# Gerador_de_Sinais.net
KiCad netlist of a schematic drawn in EAGLE
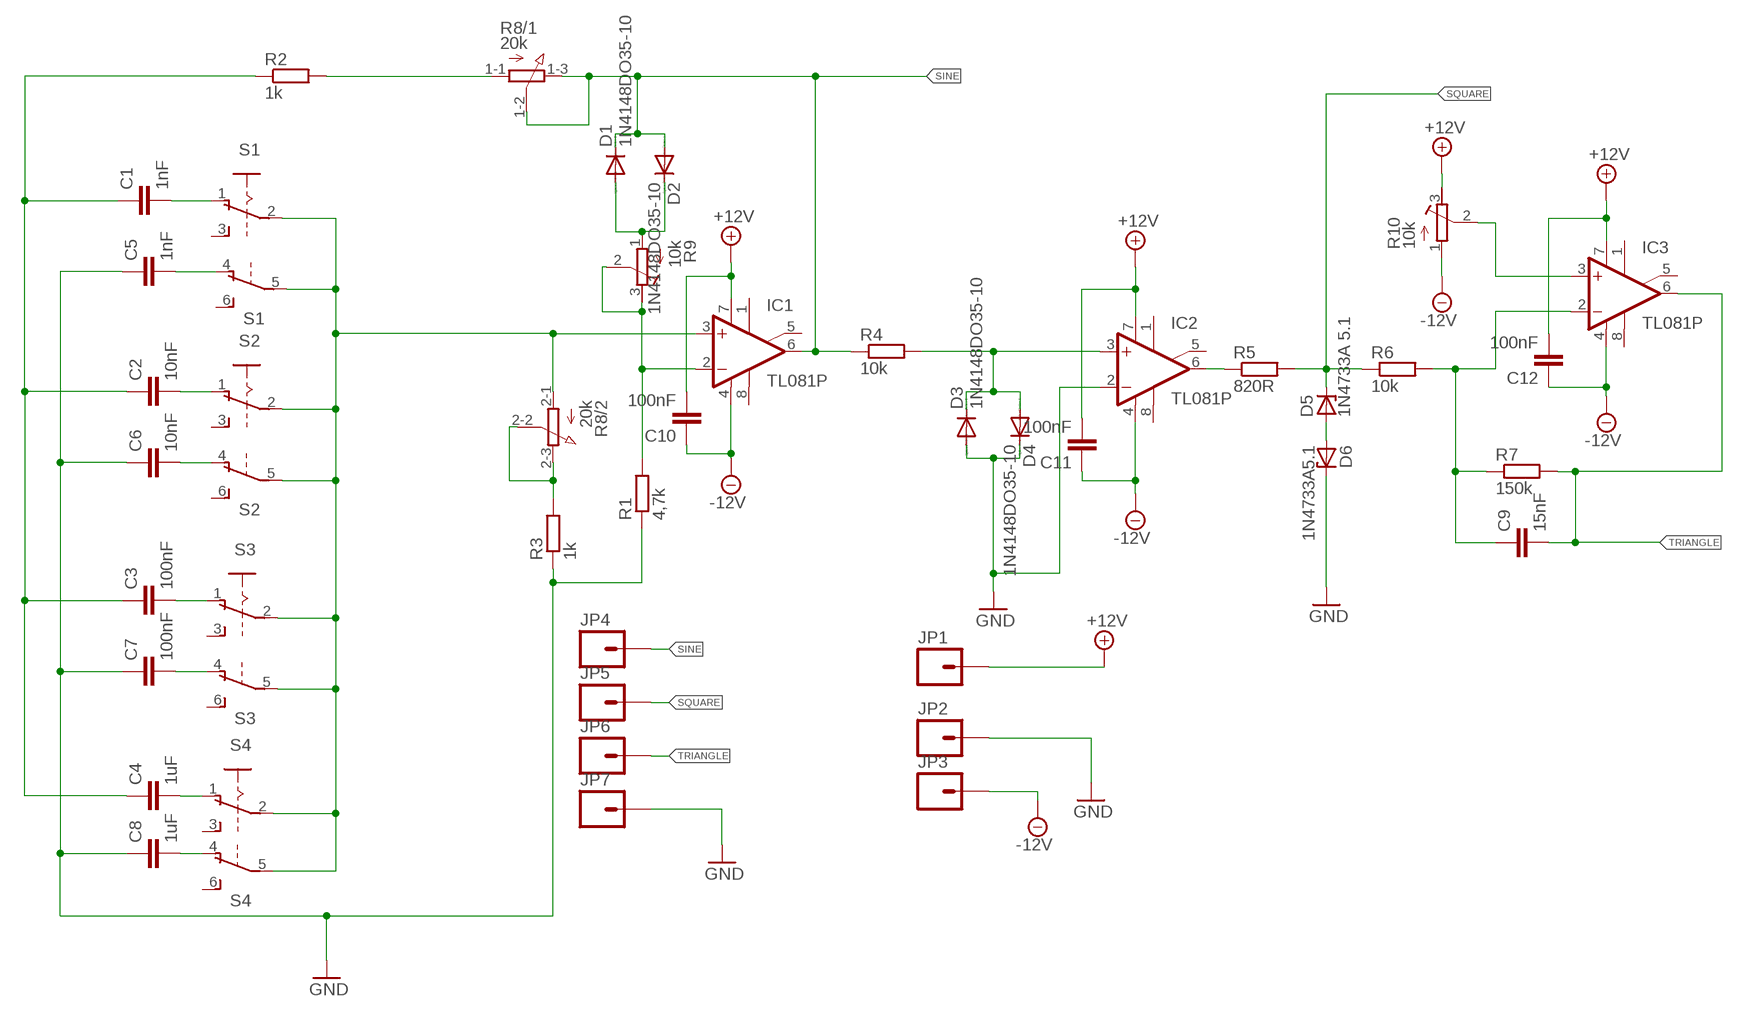
[diagram p0: schematic, sheet 1]

(export (version "E")
  (design (tool "Eeschema 10.0.6"))
  (components
    (comp (ref "C1")
      (value "1nF")
      (footprint "eagle-import:C050-050X075")
      (libsource (lib "eagle-import") (part "C-EU050-050X075"))
    )
    (comp (ref "C2")
      (value "10nF")
      (footprint "eagle-import:C050-050X075")
      (libsource (lib "eagle-import") (part "C-EU050-050X075"))
    )
    (comp (ref "C3")
      (value "100nF")
      (footprint "eagle-import:C050-050X075")
      (libsource (lib "eagle-import") (part "C-EU050-050X075"))
    )
    (comp (ref "C4")
      (value "1uF")
      (footprint "eagle-import:C050-050X075")
      (libsource (lib "eagle-import") (part "C-EU050-050X075"))
    )
    (comp (ref "C5")
      (value "1nF")
      (footprint "eagle-import:C050-050X075")
      (libsource (lib "eagle-import") (part "C-EU050-050X075"))
    )
    (comp (ref "C6")
      (value "10nF")
      (footprint "eagle-import:C050-050X075")
      (libsource (lib "eagle-import") (part "C-EU050-050X075"))
    )
    (comp (ref "C7")
      (value "100nF")
      (footprint "eagle-import:C050-050X075")
      (libsource (lib "eagle-import") (part "C-EU050-050X075"))
    )
    (comp (ref "C8")
      (value "1uF")
      (footprint "eagle-import:C050-050X075")
      (libsource (lib "eagle-import") (part "C-EU050-050X075"))
    )
    (comp (ref "C9")
      (value "15nF")
      (footprint "eagle-import:C050-050X075")
      (libsource (lib "eagle-import") (part "C-EU050-050X075"))
    )
    (comp (ref "C10")
      (value "100nF")
      (footprint "eagle-import:C050-050X075")
      (libsource (lib "eagle-import") (part "C-EU050-050X075"))
    )
    (comp (ref "C11")
      (value "100nF")
      (footprint "eagle-import:C050-050X075")
      (libsource (lib "eagle-import") (part "C-EU050-050X075"))
    )
    (comp (ref "C12")
      (value "100nF")
      (footprint "eagle-import:C050-050X075")
      (libsource (lib "eagle-import") (part "C-EU050-050X075"))
    )
    (comp (ref "D1")
      (value "1N4148DO35-10")
      (footprint "eagle-import:DO35-10")
      (libsource (lib "eagle-import") (part "1N4148DO35-10"))
    )
    (comp (ref "D2")
      (value "1N4148DO35-10")
      (footprint "eagle-import:DO35-10")
      (libsource (lib "eagle-import") (part "1N4148DO35-10"))
    )
    (comp (ref "D3")
      (value "1N4148DO35-10")
      (footprint "eagle-import:DO35-10")
      (libsource (lib "eagle-import") (part "1N4148DO35-10"))
    )
    (comp (ref "D4")
      (value "1N4148DO35-10")
      (footprint "eagle-import:DO35-10")
      (libsource (lib "eagle-import") (part "1N4148DO35-10"))
    )
    (comp (ref "D5")
      (value "1N4733A 5.1")
      (footprint "eagle-import:ZDIO-10")
      (libsource (lib "eagle-import") (part "ZENER-DIODEZD-10"))
    )
    (comp (ref "D6")
      (value "1N4733A5.1")
      (footprint "eagle-import:ZDIO-10")
      (libsource (lib "eagle-import") (part "ZENER-DIODEZD-10"))
    )
    (comp (ref "IC1")
      (value "TL081P")
      (footprint "eagle-import:DIL08")
      (libsource (lib "eagle-import") (part "TL081P"))
    )
    (comp (ref "IC2")
      (value "TL081P")
      (footprint "eagle-import:DIL08")
      (libsource (lib "eagle-import") (part "TL081P"))
    )
    (comp (ref "IC3")
      (value "TL081P")
      (footprint "eagle-import:DIL08")
      (libsource (lib "eagle-import") (part "TL081P"))
    )
    (comp (ref "JP1")
      (value "M01OFFSET")
      (footprint "eagle-import:1X01_OFFSET")
      (libsource (lib "eagle-import") (part "M01OFFSET"))
    )
    (comp (ref "JP2")
      (value "M01OFFSET")
      (footprint "eagle-import:1X01_OFFSET")
      (libsource (lib "eagle-import") (part "M01OFFSET"))
    )
    (comp (ref "JP3")
      (value "M01OFFSET")
      (footprint "eagle-import:1X01_OFFSET")
      (libsource (lib "eagle-import") (part "M01OFFSET"))
    )
    (comp (ref "JP4")
      (value "M01OFFSET")
      (footprint "eagle-import:1X01_OFFSET")
      (libsource (lib "eagle-import") (part "M01OFFSET"))
    )
    (comp (ref "JP5")
      (value "M01OFFSET")
      (footprint "eagle-import:1X01_OFFSET")
      (libsource (lib "eagle-import") (part "M01OFFSET"))
    )
    (comp (ref "JP6")
      (value "M01OFFSET")
      (footprint "eagle-import:1X01_OFFSET")
      (libsource (lib "eagle-import") (part "M01OFFSET"))
    )
    (comp (ref "JP7")
      (value "M01OFFSET")
      (footprint "eagle-import:1X01_OFFSET")
      (libsource (lib "eagle-import") (part "M01OFFSET"))
    )
    (comp (ref "R1")
      (value "4,7k")
      (footprint "eagle-import:0207_10")
      (libsource (lib "eagle-import") (part "R-EU_0207/10"))
    )
    (comp (ref "R2")
      (value "1k")
      (footprint "eagle-import:0207_10")
      (libsource (lib "eagle-import") (part "R-EU_0207/10"))
    )
    (comp (ref "R3")
      (value "1k")
      (footprint "eagle-import:0207_10")
      (libsource (lib "eagle-import") (part "R-EU_0207/10"))
    )
    (comp (ref "R4")
      (value "10k")
      (footprint "eagle-import:0207_10")
      (libsource (lib "eagle-import") (part "R-EU_0207/10"))
    )
    (comp (ref "R5")
      (value "820R")
      (footprint "eagle-import:0207_10")
      (libsource (lib "eagle-import") (part "R-EU_0207/10"))
    )
    (comp (ref "R6")
      (value "10k")
      (footprint "eagle-import:0207_10")
      (libsource (lib "eagle-import") (part "R-EU_0207/10"))
    )
    (comp (ref "R7")
      (value "150k")
      (footprint "eagle-import:0207_10")
      (libsource (lib "eagle-import") (part "R-EU_0207/10"))
    )
    (comp (ref "R8")
      (value "20k")
      (footprint "eagle-import:3RP_1610G")
      (libsource (lib "eagle-import") (part "3RP/1610G"))
    )
    (comp (ref "R9")
      (value "10k")
      (footprint "eagle-import:RTRIM3296X")
      (libsource (lib "eagle-import") (part "R-TRIMM3296X"))
    )
    (comp (ref "R10")
      (value "10k")
      (footprint "eagle-import:RTRIM3296X")
      (libsource (lib "eagle-import") (part "R-TRIMM3296X"))
    )
    (comp (ref "S1")
      (value "A68-A31")
      (footprint "eagle-import:A68-A31")
      (libsource (lib "eagle-import") (part "A68-A31"))
    )
    (comp (ref "S2")
      (value "A68-A31")
      (footprint "eagle-import:A68-A31")
      (libsource (lib "eagle-import") (part "A68-A31"))
    )
    (comp (ref "S3")
      (value "A68-A31")
      (footprint "eagle-import:A68-A31")
      (libsource (lib "eagle-import") (part "A68-A31"))
    )
    (comp (ref "S4")
      (value "A68-A31")
      (footprint "eagle-import:A68-A31")
      (libsource (lib "eagle-import") (part "A68-A31"))
    )
  )
  (nets
    (net (code "1") (name "+12V") (class "Default")
      (node (ref "C10") (pin "2") (pinfunction "2_2") (pintype "passive"))
      (node (ref "C11") (pin "2") (pinfunction "2_2") (pintype "passive"))
      (node (ref "C12") (pin "2") (pinfunction "2_2") (pintype "passive"))
      (node (ref "IC1") (pin "7") (pinfunction "V+_7") (pintype "power_in"))
      (node (ref "IC2") (pin "7") (pinfunction "V+_7") (pintype "power_in"))
      (node (ref "IC3") (pin "7") (pinfunction "V+_7") (pintype "power_in"))
      (node (ref "JP1") (pin "1") (pinfunction "1_1") (pintype "passive"))
      (node (ref "R10") (pin "3") (pinfunction "E_3") (pintype "passive"))
    )
    (net (code "2") (name "-12V") (class "Default")
      (node (ref "C10") (pin "1") (pinfunction "1_1") (pintype "passive"))
      (node (ref "C11") (pin "1") (pinfunction "1_1") (pintype "passive"))
      (node (ref "C12") (pin "1") (pinfunction "1_1") (pintype "passive"))
      (node (ref "IC1") (pin "4") (pinfunction "V-_4") (pintype "power_in"))
      (node (ref "IC2") (pin "4") (pinfunction "V-_4") (pintype "power_in"))
      (node (ref "IC3") (pin "4") (pinfunction "V-_4") (pintype "power_in"))
      (node (ref "JP3") (pin "1") (pinfunction "1_1") (pintype "passive"))
      (node (ref "R10") (pin "1") (pinfunction "A_1") (pintype "passive"))
    )
    (net (code "3") (name "GND") (class "Default")
      (node (ref "C5") (pin "1") (pinfunction "1_1") (pintype "passive"))
      (node (ref "C6") (pin "1") (pinfunction "1_1") (pintype "passive"))
      (node (ref "C7") (pin "1") (pinfunction "1_1") (pintype "passive"))
      (node (ref "C8") (pin "1") (pinfunction "1_1") (pintype "passive"))
      (node (ref "D3") (pin "A") (pinfunction "A_A") (pintype "passive"))
      (node (ref "D4") (pin "C") (pinfunction "C_C") (pintype "passive"))
      (node (ref "D6") (pin "C") (pinfunction "C_C") (pintype "passive"))
      (node (ref "IC2") (pin "2") (pinfunction "-IN_2") (pintype "input"))
      (node (ref "JP2") (pin "1") (pinfunction "1_1") (pintype "passive"))
      (node (ref "JP7") (pin "1") (pinfunction "1_1") (pintype "passive"))
      (node (ref "R1") (pin "1") (pinfunction "1_1") (pintype "passive"))
      (node (ref "R3") (pin "1") (pinfunction "1_1") (pintype "passive"))
    )
    (net (code "4") (name "Net-(C1-Pad1)") (class "Default")
      (node (ref "C1") (pin "1") (pinfunction "1_1") (pintype "passive"))
      (node (ref "C2") (pin "1") (pinfunction "1_1") (pintype "passive"))
      (node (ref "C3") (pin "1") (pinfunction "1_1") (pintype "passive"))
      (node (ref "C4") (pin "1") (pinfunction "1_1") (pintype "passive"))
      (node (ref "R2") (pin "1") (pinfunction "1_1") (pintype "passive"))
    )
    (net (code "5") (name "Net-(D5-PadA)") (class "Default")
      (node (ref "D5") (pin "A") (pinfunction "A_A") (pintype "passive"))
      (node (ref "D6") (pin "A") (pinfunction "A_A") (pintype "passive"))
    )
    (net (code "6") (name "Net-(IC1-+IN)") (class "Default")
      (node (ref "IC1") (pin "3") (pinfunction "+IN_3") (pintype "input"))
      (node (ref "R8") (pin "2-1") (pinfunction "A_2-1") (pintype "passive"))
      (node (ref "S1") (pin "2") (pinfunction "P_2") (pintype "passive"))
      (node (ref "S1") (pin "5") (pinfunction "P_5") (pintype "passive"))
      (node (ref "S2") (pin "2") (pinfunction "P_2") (pintype "passive"))
      (node (ref "S2") (pin "5") (pinfunction "P_5") (pintype "passive"))
      (node (ref "S3") (pin "2") (pinfunction "P_2") (pintype "passive"))
      (node (ref "S3") (pin "5") (pinfunction "P_5") (pintype "passive"))
      (node (ref "S4") (pin "2") (pinfunction "P_2") (pintype "passive"))
      (node (ref "S4") (pin "5") (pinfunction "P_5") (pintype "passive"))
    )
    (net (code "7") (name "Net-(IC1--IN)") (class "Default")
      (node (ref "IC1") (pin "2") (pinfunction "-IN_2") (pintype "input"))
      (node (ref "R1") (pin "2") (pinfunction "2_2") (pintype "passive"))
      (node (ref "R9") (pin "2") (pinfunction "S_2") (pintype "passive"))
      (node (ref "R9") (pin "3") (pinfunction "E_3") (pintype "passive"))
    )
    (net (code "8") (name "Net-(IC2-+IN)") (class "Default")
      (node (ref "D3") (pin "C") (pinfunction "C_C") (pintype "passive"))
      (node (ref "D4") (pin "A") (pinfunction "A_A") (pintype "passive"))
      (node (ref "IC2") (pin "3") (pinfunction "+IN_3") (pintype "input"))
      (node (ref "R4") (pin "2") (pinfunction "2_2") (pintype "passive"))
    )
    (net (code "9") (name "Net-(IC2-OUT)") (class "Default")
      (node (ref "IC2") (pin "6") (pinfunction "OUT_6") (pintype "output"))
      (node (ref "R5") (pin "1") (pinfunction "1_1") (pintype "passive"))
    )
    (net (code "10") (name "Net-(IC3-+IN)") (class "Default")
      (node (ref "IC3") (pin "3") (pinfunction "+IN_3") (pintype "input"))
      (node (ref "R10") (pin "2") (pinfunction "S_2") (pintype "passive"))
    )
    (net (code "11") (name "Net-(IC3--IN)") (class "Default")
      (node (ref "C9") (pin "1") (pinfunction "1_1") (pintype "passive"))
      (node (ref "IC3") (pin "2") (pinfunction "-IN_2") (pintype "input"))
      (node (ref "R6") (pin "2") (pinfunction "2_2") (pintype "passive"))
      (node (ref "R7") (pin "1") (pinfunction "1_1") (pintype "passive"))
    )
    (net (code "12") (name "Net-(R8A-A)") (class "Default")
      (node (ref "R2") (pin "2") (pinfunction "2_2") (pintype "passive"))
      (node (ref "R8") (pin "1-1") (pinfunction "A_1-1") (pintype "passive"))
    )
    (net (code "13") (name "Net-(R8B-E)") (class "Default")
      (node (ref "R3") (pin "2") (pinfunction "2_2") (pintype "passive"))
      (node (ref "R8") (pin "2-2") (pinfunction "S_2-2") (pintype "passive"))
      (node (ref "R8") (pin "2-3") (pinfunction "E_2-3") (pintype "passive"))
    )
    (net (code "14") (name "Net-(R9-A)") (class "Default")
      (node (ref "D1") (pin "A") (pinfunction "A_A") (pintype "passive"))
      (node (ref "D2") (pin "C") (pinfunction "C_C") (pintype "passive"))
      (node (ref "R9") (pin "1") (pinfunction "A_1") (pintype "passive"))
    )
    (net (code "15") (name "Net-(S1A-O)") (class "Default")
      (node (ref "C1") (pin "2") (pinfunction "2_2") (pintype "passive"))
      (node (ref "S1") (pin "1") (pinfunction "O_1") (pintype "passive"))
    )
    (net (code "16") (name "Net-(S1B-O)") (class "Default")
      (node (ref "C5") (pin "2") (pinfunction "2_2") (pintype "passive"))
      (node (ref "S1") (pin "4") (pinfunction "O_4") (pintype "passive"))
    )
    (net (code "17") (name "Net-(S2A-O)") (class "Default")
      (node (ref "C2") (pin "2") (pinfunction "2_2") (pintype "passive"))
      (node (ref "S2") (pin "1") (pinfunction "O_1") (pintype "passive"))
    )
    (net (code "18") (name "Net-(S2B-O)") (class "Default")
      (node (ref "C6") (pin "2") (pinfunction "2_2") (pintype "passive"))
      (node (ref "S2") (pin "4") (pinfunction "O_4") (pintype "passive"))
    )
    (net (code "19") (name "Net-(S3A-O)") (class "Default")
      (node (ref "C3") (pin "2") (pinfunction "2_2") (pintype "passive"))
      (node (ref "S3") (pin "1") (pinfunction "O_1") (pintype "passive"))
    )
    (net (code "20") (name "Net-(S3B-O)") (class "Default")
      (node (ref "C7") (pin "2") (pinfunction "2_2") (pintype "passive"))
      (node (ref "S3") (pin "4") (pinfunction "O_4") (pintype "passive"))
    )
    (net (code "21") (name "Net-(S4A-O)") (class "Default")
      (node (ref "C4") (pin "2") (pinfunction "2_2") (pintype "passive"))
      (node (ref "S4") (pin "1") (pinfunction "O_1") (pintype "passive"))
    )
    (net (code "22") (name "Net-(S4B-O)") (class "Default")
      (node (ref "C8") (pin "2") (pinfunction "2_2") (pintype "passive"))
      (node (ref "S4") (pin "4") (pinfunction "O_4") (pintype "passive"))
    )
    (net (code "23") (name "SINE") (class "Default")
      (node (ref "D1") (pin "C") (pinfunction "C_C") (pintype "passive"))
      (node (ref "D2") (pin "A") (pinfunction "A_A") (pintype "passive"))
      (node (ref "IC1") (pin "6") (pinfunction "OUT_6") (pintype "output"))
      (node (ref "JP4") (pin "1") (pinfunction "1_1") (pintype "passive"))
      (node (ref "R4") (pin "1") (pinfunction "1_1") (pintype "passive"))
      (node (ref "R8") (pin "1-2") (pinfunction "S_1-2") (pintype "passive"))
      (node (ref "R8") (pin "1-3") (pinfunction "E_1-3") (pintype "passive"))
    )
    (net (code "24") (name "SQUARE") (class "Default")
      (node (ref "D5") (pin "C") (pinfunction "C_C") (pintype "passive"))
      (node (ref "JP5") (pin "1") (pinfunction "1_1") (pintype "passive"))
      (node (ref "R5") (pin "2") (pinfunction "2_2") (pintype "passive"))
      (node (ref "R6") (pin "1") (pinfunction "1_1") (pintype "passive"))
    )
    (net (code "25") (name "TRIANGLE") (class "Default")
      (node (ref "C9") (pin "2") (pinfunction "2_2") (pintype "passive"))
      (node (ref "IC3") (pin "6") (pinfunction "OUT_6") (pintype "output"))
      (node (ref "JP6") (pin "1") (pinfunction "1_1") (pintype "passive"))
      (node (ref "R7") (pin "2") (pinfunction "2_2") (pintype "passive"))
    )
    (net (code "26") (name "unconnected-(IC1-ON1-Pad1)") (class "Default")
      (node (ref "IC1") (pin "1") (pinfunction "ON1_1") (pintype "passive"))
    )
    (net (code "27") (name "unconnected-(IC1-ON2-Pad5)") (class "Default")
      (node (ref "IC1") (pin "5") (pinfunction "ON2_5") (pintype "passive"))
    )
    (net (code "28") (name "unconnected-(IC1-OPT-Pad8)") (class "Default")
      (node (ref "IC1") (pin "8") (pinfunction "OPT_8") (pintype "passive"))
    )
    (net (code "29") (name "unconnected-(IC2-ON1-Pad1)") (class "Default")
      (node (ref "IC2") (pin "1") (pinfunction "ON1_1") (pintype "passive"))
    )
    (net (code "30") (name "unconnected-(IC2-ON2-Pad5)") (class "Default")
      (node (ref "IC2") (pin "5") (pinfunction "ON2_5") (pintype "passive"))
    )
    (net (code "31") (name "unconnected-(IC2-OPT-Pad8)") (class "Default")
      (node (ref "IC2") (pin "8") (pinfunction "OPT_8") (pintype "passive"))
    )
    (net (code "32") (name "unconnected-(IC3-ON1-Pad1)") (class "Default")
      (node (ref "IC3") (pin "1") (pinfunction "ON1_1") (pintype "passive"))
    )
    (net (code "33") (name "unconnected-(IC3-ON2-Pad5)") (class "Default")
      (node (ref "IC3") (pin "5") (pinfunction "ON2_5") (pintype "passive"))
    )
    (net (code "34") (name "unconnected-(IC3-OPT-Pad8)") (class "Default")
      (node (ref "IC3") (pin "8") (pinfunction "OPT_8") (pintype "passive"))
    )
    (net (code "35") (name "unconnected-(S1A-S-Pad3)") (class "Default")
      (node (ref "S1") (pin "3") (pinfunction "S_3") (pintype "passive"))
    )
    (net (code "36") (name "unconnected-(S1B-S-Pad6)") (class "Default")
      (node (ref "S1") (pin "6") (pinfunction "S_6") (pintype "passive"))
    )
    (net (code "37") (name "unconnected-(S2A-S-Pad3)") (class "Default")
      (node (ref "S2") (pin "3") (pinfunction "S_3") (pintype "passive"))
    )
    (net (code "38") (name "unconnected-(S2B-S-Pad6)") (class "Default")
      (node (ref "S2") (pin "6") (pinfunction "S_6") (pintype "passive"))
    )
    (net (code "39") (name "unconnected-(S3A-S-Pad3)") (class "Default")
      (node (ref "S3") (pin "3") (pinfunction "S_3") (pintype "passive"))
    )
    (net (code "40") (name "unconnected-(S3B-S-Pad6)") (class "Default")
      (node (ref "S3") (pin "6") (pinfunction "S_6") (pintype "passive"))
    )
    (net (code "41") (name "unconnected-(S4A-S-Pad3)") (class "Default")
      (node (ref "S4") (pin "3") (pinfunction "S_3") (pintype "passive"))
    )
    (net (code "42") (name "unconnected-(S4B-S-Pad6)") (class "Default")
      (node (ref "S4") (pin "6") (pinfunction "S_6") (pintype "passive"))
    )
  )
)
